# TOOLKIT_CON_ETIQ.net
KiCad netlist of a schematic drawn in EAGLE
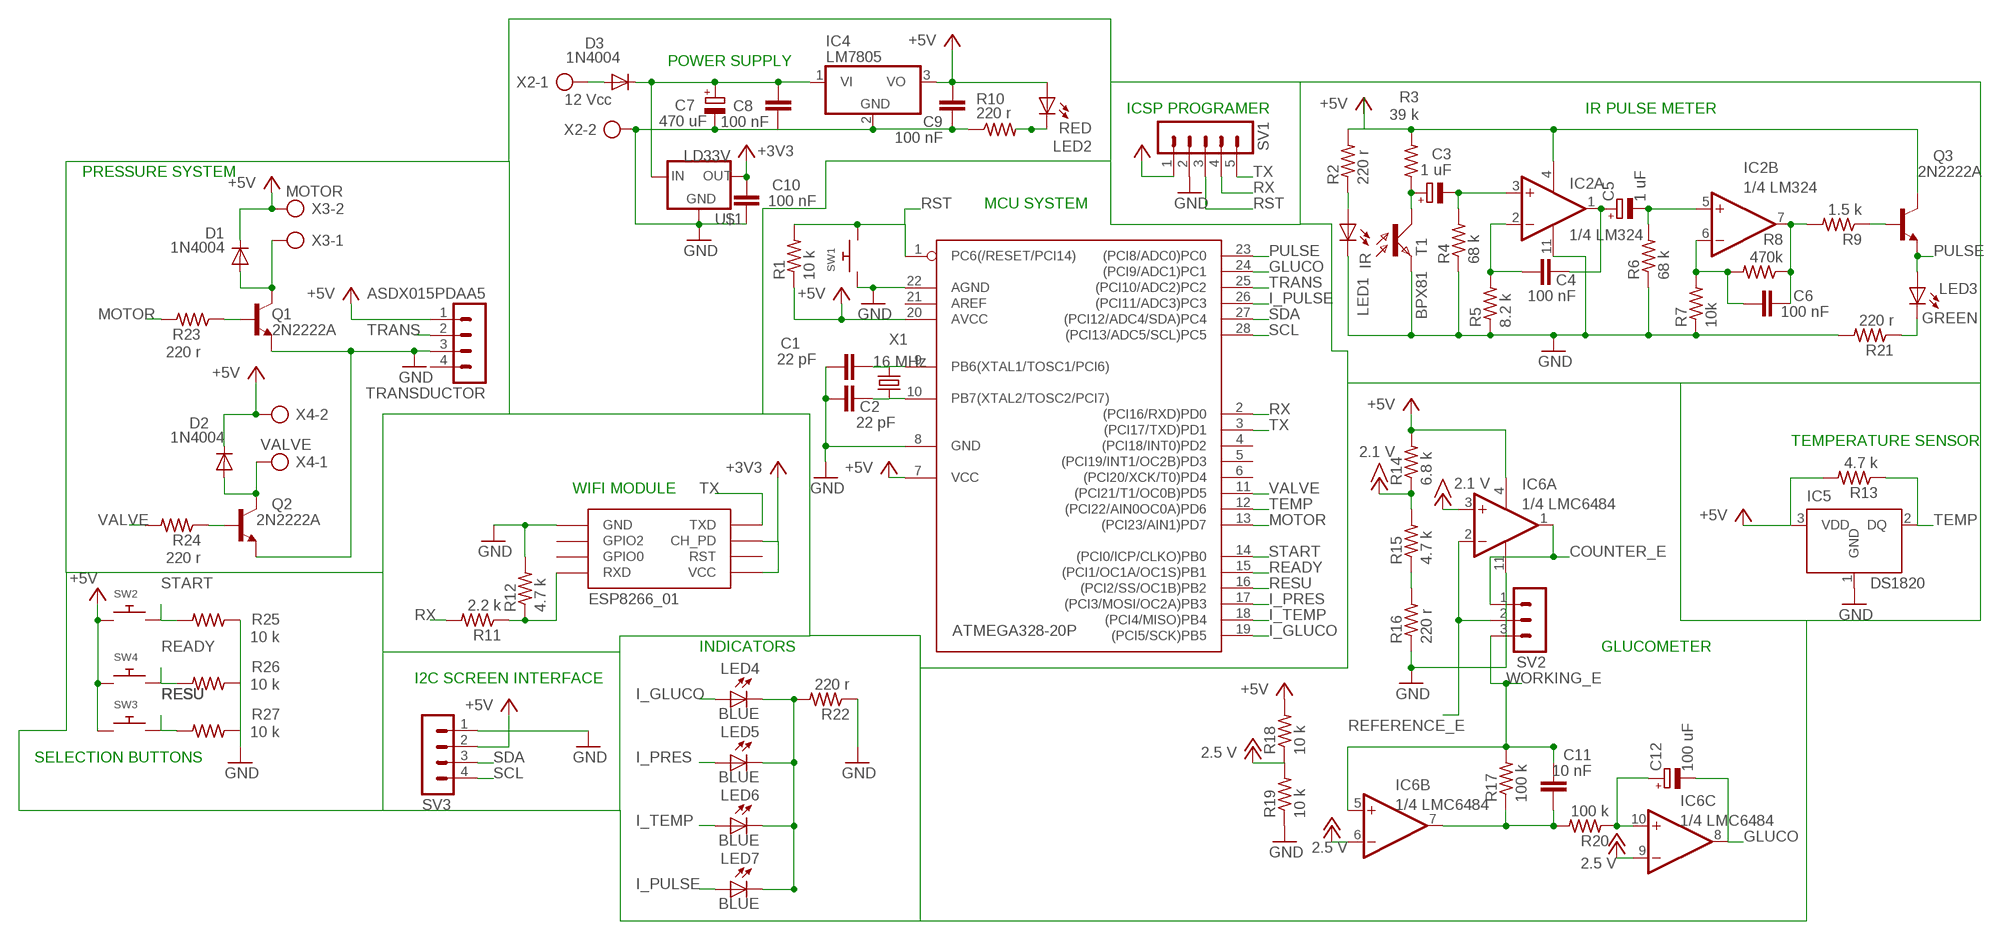
[diagram p0: schematic, sheet 1]

(export (version "E")
  (design (tool "Eeschema 10.0.6"))
  (components
    (comp (ref "C1")
      (value "22 pF")
      (footprint "eagle-import:C050-024X044")
      (libsource (lib "eagle-import") (part "C-EU050-024X044"))
    )
    (comp (ref "C2")
      (value "22 pF")
      (footprint "eagle-import:C050-024X044")
      (libsource (lib "eagle-import") (part "C-EU050-024X044"))
    )
    (comp (ref "C3")
      (value "1 uF")
      (footprint "eagle-import:E2,5-6E")
      (libsource (lib "eagle-import") (part "CPOL-EUE2,5-6E"))
    )
    (comp (ref "C4")
      (value "100 nF")
      (footprint "eagle-import:C050-025X075")
      (libsource (lib "eagle-import") (part "C-EU050-025X075"))
    )
    (comp (ref "C5")
      (value "1 uF")
      (footprint "eagle-import:E2,5-6E")
      (libsource (lib "eagle-import") (part "CPOL-EUE2,5-6E"))
    )
    (comp (ref "C6")
      (value "100 nF")
      (footprint "eagle-import:C050-025X075")
      (libsource (lib "eagle-import") (part "C-EU050-025X075"))
    )
    (comp (ref "C7")
      (value "470 uF")
      (footprint "eagle-import:E2,5-6E")
      (libsource (lib "eagle-import") (part "CPOL-EUE2,5-6E"))
    )
    (comp (ref "C8")
      (value "100 nF")
      (footprint "eagle-import:C050-025X075")
      (libsource (lib "eagle-import") (part "C-EU050-025X075"))
    )
    (comp (ref "C9")
      (value "100 nF")
      (footprint "eagle-import:C050-025X075")
      (libsource (lib "eagle-import") (part "C-EU050-025X075"))
    )
    (comp (ref "C10")
      (value "100 nF")
      (footprint "eagle-import:C050-025X075")
      (libsource (lib "eagle-import") (part "C-EU050-025X075"))
    )
    (comp (ref "C11")
      (value "10 nF")
      (footprint "eagle-import:C050-025X075")
      (libsource (lib "eagle-import") (part "C-EU050-025X075"))
    )
    (comp (ref "C12")
      (value "100 uF")
      (footprint "eagle-import:E2,5-6E")
      (libsource (lib "eagle-import") (part "CPOL-EUE2,5-6E"))
    )
    (comp (ref "D1")
      (value "1N4004")
      (footprint "eagle-import:DO41-10")
      (libsource (lib "eagle-import") (part "1N4004"))
    )
    (comp (ref "D2")
      (value "1N4004")
      (footprint "eagle-import:DO41-10")
      (libsource (lib "eagle-import") (part "1N4004"))
    )
    (comp (ref "D3")
      (value "1N4004")
      (footprint "eagle-import:DO41-10")
      (libsource (lib "eagle-import") (part "1N4004"))
    )
    (comp (ref "IC1")
      (value "ATMEGA328-20P")
      (footprint "eagle-import:DIL28-3")
      (libsource (lib "eagle-import") (part "ATMEGA328P-20"))
    )
    (comp (ref "IC2")
      (value "1/4 LM324")
      (footprint "eagle-import:DIL14")
      (libsource (lib "eagle-import") (part "LM324N"))
    )
    (comp (ref "IC4")
      (value "LM7805")
      (footprint "eagle-import:TO220V")
      (libsource (lib "eagle-import") (part "78TV05"))
    )
    (comp (ref "IC5")
      (value "DS1820")
      (footprint "eagle-import:TO-92")
      (libsource (lib "eagle-import") (part "DS1820"))
    )
    (comp (ref "IC6")
      (value "1/4 LMC6484")
      (footprint "eagle-import:DIL14")
      (libsource (lib "eagle-import") (part "LM2902N"))
    )
    (comp (ref "LED1")
      (value "IR")
      (footprint "eagle-import:LED3MM")
      (libsource (lib "eagle-import") (part "LED3MM"))
    )
    (comp (ref "LED2")
      (value "RED")
      (footprint "eagle-import:LED3MM")
      (libsource (lib "eagle-import") (part "LED3MM"))
    )
    (comp (ref "LED3")
      (value "GREEN")
      (footprint "eagle-import:LED3MM")
      (libsource (lib "eagle-import") (part "LED3MM"))
    )
    (comp (ref "LED4")
      (value "BLUE")
      (footprint "eagle-import:LED3MM")
      (libsource (lib "eagle-import") (part "LED3MM"))
    )
    (comp (ref "LED5")
      (value "BLUE")
      (footprint "eagle-import:LED3MM")
      (libsource (lib "eagle-import") (part "LED3MM"))
    )
    (comp (ref "LED6")
      (value "BLUE")
      (footprint "eagle-import:LED3MM")
      (libsource (lib "eagle-import") (part "LED3MM"))
    )
    (comp (ref "LED7")
      (value "BLUE")
      (footprint "eagle-import:LED3MM")
      (libsource (lib "eagle-import") (part "LED3MM"))
    )
    (comp (ref "Q1")
      (value "2N2222A")
      (footprint "eagle-import:TO92-EBC")
      (libsource (lib "eagle-import") (part "-NPN-TO92-EBC2N2222"))
    )
    (comp (ref "Q2")
      (value "2N2222A")
      (footprint "eagle-import:TO92-EBC")
      (libsource (lib "eagle-import") (part "-NPN-TO92-EBC2N2222"))
    )
    (comp (ref "Q3")
      (value "2N2222A")
      (footprint "eagle-import:TO92-EBC")
      (libsource (lib "eagle-import") (part "-NPN-TO92-EBC2N2222"))
    )
    (comp (ref "R1")
      (value "10 k")
      (footprint "eagle-import:0207_10")
      (libsource (lib "eagle-import") (part "R-US_0207/10"))
    )
    (comp (ref "R2")
      (value "220 r")
      (footprint "eagle-import:0207_10")
      (libsource (lib "eagle-import") (part "R-US_0207/10"))
    )
    (comp (ref "R3")
      (value "39 k")
      (footprint "eagle-import:0207_10")
      (libsource (lib "eagle-import") (part "R-US_0207/10"))
    )
    (comp (ref "R4")
      (value "68 k")
      (footprint "eagle-import:0207_10")
      (libsource (lib "eagle-import") (part "R-US_0207/10"))
    )
    (comp (ref "R5")
      (value "8.2 k")
      (footprint "eagle-import:0207_10")
      (libsource (lib "eagle-import") (part "R-US_0207/10"))
    )
    (comp (ref "R6")
      (value "68 k")
      (footprint "eagle-import:0207_10")
      (libsource (lib "eagle-import") (part "R-US_0207/10"))
    )
    (comp (ref "R7")
      (value "10k")
      (footprint "eagle-import:0207_10")
      (libsource (lib "eagle-import") (part "R-US_0207/10"))
    )
    (comp (ref "R8")
      (value "470k")
      (footprint "eagle-import:0207_10")
      (libsource (lib "eagle-import") (part "R-US_0207/10"))
    )
    (comp (ref "R9")
      (value "1.5 k")
      (footprint "eagle-import:0207_10")
      (libsource (lib "eagle-import") (part "R-US_0207/10"))
    )
    (comp (ref "R10")
      (value "220 r")
      (footprint "eagle-import:0207_10")
      (libsource (lib "eagle-import") (part "R-US_0207/10"))
    )
    (comp (ref "R11")
      (value "2.2 k")
      (footprint "eagle-import:0207_10")
      (libsource (lib "eagle-import") (part "R-US_0207/10"))
    )
    (comp (ref "R12")
      (value "4.7 k")
      (footprint "eagle-import:0207_10")
      (libsource (lib "eagle-import") (part "R-US_0207/10"))
    )
    (comp (ref "R13")
      (value "4.7 k")
      (footprint "eagle-import:0207_10")
      (libsource (lib "eagle-import") (part "R-US_0207/10"))
    )
    (comp (ref "R14")
      (value "6.8 k")
      (footprint "eagle-import:0207_10")
      (libsource (lib "eagle-import") (part "R-US_0207/10"))
    )
    (comp (ref "R15")
      (value "4.7 k")
      (footprint "eagle-import:0207_10")
      (libsource (lib "eagle-import") (part "R-US_0207/10"))
    )
    (comp (ref "R16")
      (value "220 r")
      (footprint "eagle-import:0207_10")
      (libsource (lib "eagle-import") (part "R-US_0207/10"))
    )
    (comp (ref "R17")
      (value "100 k")
      (footprint "eagle-import:0207_10")
      (libsource (lib "eagle-import") (part "R-US_0207/10"))
    )
    (comp (ref "R18")
      (value "10 k")
      (footprint "eagle-import:0207_10")
      (libsource (lib "eagle-import") (part "R-US_0207/10"))
    )
    (comp (ref "R19")
      (value "10 k")
      (footprint "eagle-import:0207_10")
      (libsource (lib "eagle-import") (part "R-US_0207/10"))
    )
    (comp (ref "R20")
      (value "100 k")
      (footprint "eagle-import:0207_10")
      (libsource (lib "eagle-import") (part "R-US_0207/10"))
    )
    (comp (ref "R21")
      (value "220 r")
      (footprint "eagle-import:0207_10")
      (libsource (lib "eagle-import") (part "R-US_0207/10"))
    )
    (comp (ref "R22")
      (value "220 r")
      (footprint "eagle-import:0207_10")
      (libsource (lib "eagle-import") (part "R-US_0207/10"))
    )
    (comp (ref "R23")
      (value "220 r")
      (footprint "eagle-import:0207_10")
      (libsource (lib "eagle-import") (part "R-US_0207/10"))
    )
    (comp (ref "R24")
      (value "220 r")
      (footprint "eagle-import:0207_10")
      (libsource (lib "eagle-import") (part "R-US_0207/10"))
    )
    (comp (ref "R25")
      (value "10 k")
      (footprint "eagle-import:0207_10")
      (libsource (lib "eagle-import") (part "R-US_0207/10"))
    )
    (comp (ref "R26")
      (value "10 k")
      (footprint "eagle-import:0207_10")
      (libsource (lib "eagle-import") (part "R-US_0207/10"))
    )
    (comp (ref "R27")
      (value "10 k")
      (footprint "eagle-import:0207_10")
      (libsource (lib "eagle-import") (part "R-US_0207/10"))
    )
    (comp (ref "SV1")
      (value "MA05-1")
      (footprint "eagle-import:MA05-1")
      (libsource (lib "eagle-import") (part "MA05-1"))
    )
    (comp (ref "SV2")
      (value "MA03-1")
      (footprint "eagle-import:MA03-1")
      (libsource (lib "eagle-import") (part "MA03-1"))
    )
    (comp (ref "SV3")
      (value "MA04-1")
      (footprint "eagle-import:MA04-1")
      (libsource (lib "eagle-import") (part "MA04-1"))
    )
    (comp (ref "SW1")
      (value "SWITCH_PUSHBUTTONEVQ-PE")
      (footprint "eagle-import:TACT_PANA-EVQ")
      (libsource (lib "eagle-import") (part "SWITCH_PUSHBUTTONEVQ-PE"))
    )
    (comp (ref "SW2")
      (value "SWITCH_PUSHBUTTONEVQ-PE")
      (footprint "eagle-import:TACT_PANA-EVQ")
      (libsource (lib "eagle-import") (part "SWITCH_PUSHBUTTONEVQ-PE"))
    )
    (comp (ref "SW3")
      (value "SWITCH_PUSHBUTTONEVQ-PE")
      (footprint "eagle-import:TACT_PANA-EVQ")
      (libsource (lib "eagle-import") (part "SWITCH_PUSHBUTTONEVQ-PE"))
    )
    (comp (ref "SW4")
      (value "SWITCH_PUSHBUTTONEVQ-PE")
      (footprint "eagle-import:TACT_PANA-EVQ")
      (libsource (lib "eagle-import") (part "SWITCH_PUSHBUTTONEVQ-PE"))
    )
    (comp (ref "T1")
      (value "BPX81")
      (footprint "eagle-import:BPX81")
      (libsource (lib "eagle-import") (part "BPX81"))
    )
    (comp (ref "TRANSDUCTOR")
      (value "ASDX015PDAA5")
      (footprint "eagle-import:MA04-1")
      (libsource (lib "eagle-import") (part "MA04-1"))
    )
    (comp (ref "U$1")
      (value "LD33V")
      (footprint "eagle-import:LD1117V33")
      (libsource (lib "eagle-import") (part "LD1117V33"))
    )
    (comp (ref "U$2")
      (value "ESP8266_01")
      (footprint "eagle-import:ESP01")
      (libsource (lib "eagle-import") (part "ESP01"))
    )
    (comp (ref "X1")
      (value "16 MHz")
      (footprint "eagle-import:HC18U-V")
      (libsource (lib "eagle-import") (part "CRYSTALHC18U-V"))
    )
    (comp (ref "X2")
      (value "12 Vcc")
      (footprint "eagle-import:AK500_2")
      (libsource (lib "eagle-import") (part "AK500/2"))
    )
    (comp (ref "X3")
      (value "MOTOR")
      (footprint "eagle-import:AK500_2")
      (libsource (lib "eagle-import") (part "AK500/2"))
    )
    (comp (ref "X4")
      (value "VALVE")
      (footprint "eagle-import:AK500_2")
      (libsource (lib "eagle-import") (part "AK500/2"))
    )
  )
  (nets
    (net (code "1") (name "+3V3") (class "Default")
      (node (ref "C10") (pin "2") (pinfunction "2_2") (pintype "passive"))
      (node (ref "U$1") (pin "OUT") (pinfunction "OUT_OUT") (pintype "output"))
      (node (ref "U$2") (pin "CH_PD") (pinfunction "CH_PD_CH_PD") (pintype "bidirectional"))
      (node (ref "U$2") (pin "VCC") (pinfunction "VCC_VCC") (pintype "bidirectional"))
    )
    (net (code "2") (name "+5V") (class "Default")
      (node (ref "C9") (pin "2") (pinfunction "2_2") (pintype "passive"))
      (node (ref "D1") (pin "C") (pinfunction "C_C") (pintype "passive"))
      (node (ref "D2") (pin "C") (pinfunction "C_C") (pintype "passive"))
      (node (ref "IC1") (pin "20") (pinfunction "AVCC_20") (pintype "bidirectional"))
      (node (ref "IC1") (pin "7") (pinfunction "VCC_7") (pintype "bidirectional"))
      (node (ref "IC2") (pin "4") (pinfunction "V+_4") (pintype "power_in"))
      (node (ref "IC4") (pin "3") (pinfunction "VO_3") (pintype "passive"))
      (node (ref "IC5") (pin "3") (pinfunction "VDD_3") (pintype "input"))
      (node (ref "IC6") (pin "4") (pinfunction "V+_4") (pintype "power_in"))
      (node (ref "LED2") (pin "A") (pinfunction "A_A") (pintype "passive"))
      (node (ref "Q3") (pin "C") (pinfunction "C_C") (pintype "passive"))
      (node (ref "R1") (pin "1") (pinfunction "1_1") (pintype "passive"))
      (node (ref "R13") (pin "2") (pinfunction "2_2") (pintype "passive"))
      (node (ref "R14") (pin "2") (pinfunction "2_2") (pintype "passive"))
      (node (ref "R18") (pin "2") (pinfunction "2_2") (pintype "passive"))
      (node (ref "R2") (pin "2") (pinfunction "2_2") (pintype "passive"))
      (node (ref "R3") (pin "2") (pinfunction "2_2") (pintype "passive"))
      (node (ref "SV1") (pin "1") (pinfunction "1_1") (pintype "passive"))
      (node (ref "SV3") (pin "2") (pinfunction "2_2") (pintype "passive"))
      (node (ref "SW2") (pin "P$1") (pinfunction "P$1_P$1") (pintype "passive"))
      (node (ref "SW3") (pin "P$1") (pinfunction "P$1_P$1") (pintype "passive"))
      (node (ref "SW4") (pin "P$1") (pinfunction "P$1_P$1") (pintype "passive"))
      (node (ref "TRANSDUCTOR") (pin "1") (pinfunction "1_1") (pintype "passive"))
      (node (ref "X3") (pin "2") (pinfunction "KL_2") (pintype "passive"))
      (node (ref "X4") (pin "2") (pinfunction "KL_2") (pintype "passive"))
    )
    (net (code "3") (name "/COUNTER_E") (class "Default")
      (node (ref "IC6") (pin "1") (pinfunction "OUT_1") (pintype "output"))
      (node (ref "SV2") (pin "1") (pinfunction "1_1") (pintype "passive"))
    )
    (net (code "4") (name "/GLUCO") (class "Default")
      (node (ref "C12") (pin "-") (pinfunction "-_-") (pintype "passive"))
      (node (ref "IC1") (pin "24") (pinfunction "(PCI9/ADC1)PC1_24") (pintype "bidirectional"))
      (node (ref "IC6") (pin "8") (pinfunction "OUT_8") (pintype "output"))
    )
    (net (code "5") (name "/I_GLUCO") (class "Default")
      (node (ref "IC1") (pin "19") (pinfunction "(PCI5/SCK)PB5_19") (pintype "bidirectional"))
      (node (ref "LED4") (pin "A") (pinfunction "A_A") (pintype "passive"))
    )
    (net (code "6") (name "/I_PRES") (class "Default")
      (node (ref "IC1") (pin "17") (pinfunction "(PCI3/MOSI/OC2A)PB3_17") (pintype "bidirectional"))
      (node (ref "LED5") (pin "A") (pinfunction "A_A") (pintype "passive"))
    )
    (net (code "7") (name "/I_PULSE") (class "Default")
      (node (ref "IC1") (pin "26") (pinfunction "(PCI11/ADC3)PC3_26") (pintype "bidirectional"))
      (node (ref "LED7") (pin "A") (pinfunction "A_A") (pintype "passive"))
    )
    (net (code "8") (name "/I_TEMP") (class "Default")
      (node (ref "IC1") (pin "18") (pinfunction "(PCI4/MISO)PB4_18") (pintype "bidirectional"))
      (node (ref "LED6") (pin "A") (pinfunction "A_A") (pintype "passive"))
    )
    (net (code "9") (name "/MOTOR") (class "Default")
      (node (ref "IC1") (pin "13") (pinfunction "(PCI23/AIN1)PD7_13") (pintype "bidirectional"))
      (node (ref "R23") (pin "2") (pinfunction "2_2") (pintype "passive"))
    )
    (net (code "10") (name "/PULSE") (class "Default")
      (node (ref "IC1") (pin "23") (pinfunction "(PCI8/ADC0)PC0_23") (pintype "bidirectional"))
      (node (ref "LED3") (pin "A") (pinfunction "A_A") (pintype "passive"))
      (node (ref "Q3") (pin "E") (pinfunction "E_E") (pintype "passive"))
    )
    (net (code "11") (name "/READY") (class "Default")
      (node (ref "IC1") (pin "15") (pinfunction "(PCI1/OC1A/OC1S)PB1_15") (pintype "bidirectional"))
      (node (ref "R26") (pin "2") (pinfunction "2_2") (pintype "passive"))
      (node (ref "SW4") (pin "P$2") (pinfunction "P$2_P$2") (pintype "passive"))
    )
    (net (code "12") (name "/REFERENCE_E") (class "Default")
      (node (ref "IC6") (pin "2") (pinfunction "-IN_2") (pintype "input"))
      (node (ref "SV2") (pin "2") (pinfunction "2_2") (pintype "passive"))
    )
    (net (code "13") (name "/RESU") (class "Default")
      (node (ref "IC1") (pin "16") (pinfunction "(PCI2/SS/OC1B)PB2_16") (pintype "bidirectional"))
      (node (ref "R27") (pin "2") (pinfunction "2_2") (pintype "passive"))
      (node (ref "SW3") (pin "P$2") (pinfunction "P$2_P$2") (pintype "passive"))
    )
    (net (code "14") (name "/RST") (class "Default")
      (node (ref "IC1") (pin "1") (pinfunction "PC6(/RESET/PCI14)_1") (pintype "bidirectional"))
      (node (ref "R1") (pin "2") (pinfunction "2_2") (pintype "passive"))
      (node (ref "SV1") (pin "3") (pinfunction "3_3") (pintype "passive"))
      (node (ref "SW1") (pin "P$2") (pinfunction "P$2_P$2") (pintype "passive"))
    )
    (net (code "15") (name "/RX") (class "Default")
      (node (ref "IC1") (pin "2") (pinfunction "(PCI16/RXD)PD0_2") (pintype "bidirectional"))
      (node (ref "R11") (pin "2") (pinfunction "2_2") (pintype "passive"))
      (node (ref "SV1") (pin "4") (pinfunction "4_4") (pintype "passive"))
    )
    (net (code "16") (name "/SCL") (class "Default")
      (node (ref "IC1") (pin "28") (pinfunction "(PCI13/ADC5/SCL)PC5_28") (pintype "bidirectional"))
      (node (ref "SV3") (pin "4") (pinfunction "4_4") (pintype "passive"))
    )
    (net (code "17") (name "/SDA") (class "Default")
      (node (ref "IC1") (pin "27") (pinfunction "(PCI12/ADC4/SDA)PC4_27") (pintype "bidirectional"))
      (node (ref "SV3") (pin "3") (pinfunction "3_3") (pintype "passive"))
    )
    (net (code "18") (name "/START") (class "Default")
      (node (ref "IC1") (pin "14") (pinfunction "(PCI0/ICP/CLKO)PB0_14") (pintype "bidirectional"))
      (node (ref "R25") (pin "2") (pinfunction "2_2") (pintype "passive"))
      (node (ref "SW2") (pin "P$2") (pinfunction "P$2_P$2") (pintype "passive"))
    )
    (net (code "19") (name "/TEMP") (class "Default")
      (node (ref "IC1") (pin "12") (pinfunction "(PCI22/AIN0OC0A)PD6_12") (pintype "bidirectional"))
      (node (ref "IC5") (pin "2") (pinfunction "DQ_2") (pintype "output"))
      (node (ref "R13") (pin "1") (pinfunction "1_1") (pintype "passive"))
    )
    (net (code "20") (name "/TRANS") (class "Default")
      (node (ref "IC1") (pin "25") (pinfunction "(PCI10/ADC2)PC2_25") (pintype "bidirectional"))
      (node (ref "TRANSDUCTOR") (pin "2") (pinfunction "2_2") (pintype "passive"))
    )
    (net (code "21") (name "/TX") (class "Default")
      (node (ref "IC1") (pin "3") (pinfunction "(PCI17/TXD)PD1_3") (pintype "bidirectional"))
      (node (ref "SV1") (pin "5") (pinfunction "5_5") (pintype "passive"))
      (node (ref "U$2") (pin "TX") (pinfunction "TXD_TX") (pintype "bidirectional"))
    )
    (net (code "22") (name "/VALVE") (class "Default")
      (node (ref "IC1") (pin "11") (pinfunction "(PCI21/T1/OC0B)PD5_11") (pintype "bidirectional"))
      (node (ref "R24") (pin "2") (pinfunction "2_2") (pintype "passive"))
    )
    (net (code "23") (name "/WORKING_E") (class "Default")
      (node (ref "C11") (pin "2") (pinfunction "2_2") (pintype "passive"))
      (node (ref "IC6") (pin "5") (pinfunction "+IN_5") (pintype "input"))
      (node (ref "R17") (pin "2") (pinfunction "2_2") (pintype "passive"))
      (node (ref "SV2") (pin "3") (pinfunction "3_3") (pintype "passive"))
    )
    (net (code "24") (name "2.1 V") (class "Default")
      (node (ref "IC6") (pin "3") (pinfunction "+IN_3") (pintype "input"))
      (node (ref "R14") (pin "1") (pinfunction "1_1") (pintype "passive"))
      (node (ref "R15") (pin "2") (pinfunction "2_2") (pintype "passive"))
    )
    (net (code "25") (name "2.5 V") (class "Default")
      (node (ref "IC6") (pin "6") (pinfunction "-IN_6") (pintype "input"))
      (node (ref "IC6") (pin "9") (pinfunction "-IN_9") (pintype "input"))
      (node (ref "R18") (pin "1") (pinfunction "1_1") (pintype "passive"))
      (node (ref "R19") (pin "2") (pinfunction "2_2") (pintype "passive"))
    )
    (net (code "26") (name "GND") (class "Default")
      (node (ref "C1") (pin "1") (pinfunction "1_1") (pintype "passive"))
      (node (ref "C10") (pin "1") (pinfunction "1_1") (pintype "passive"))
      (node (ref "C2") (pin "1") (pinfunction "1_1") (pintype "passive"))
      (node (ref "C7") (pin "-") (pinfunction "-_-") (pintype "passive"))
      (node (ref "C8") (pin "1") (pinfunction "1_1") (pintype "passive"))
      (node (ref "C9") (pin "1") (pinfunction "1_1") (pintype "passive"))
      (node (ref "IC1") (pin "22") (pinfunction "AGND_22") (pintype "bidirectional"))
      (node (ref "IC1") (pin "8") (pinfunction "GND_8") (pintype "bidirectional"))
      (node (ref "IC2") (pin "11") (pinfunction "V-_11") (pintype "power_in"))
      (node (ref "IC4") (pin "2") (pinfunction "GND_2") (pintype "passive"))
      (node (ref "IC5") (pin "1") (pinfunction "GND_1") (pintype "power_in"))
      (node (ref "IC6") (pin "11") (pinfunction "V-_11") (pintype "power_in"))
      (node (ref "LED1") (pin "K") (pinfunction "C_K") (pintype "passive"))
      (node (ref "Q1") (pin "E") (pinfunction "E_E") (pintype "passive"))
      (node (ref "Q2") (pin "E") (pinfunction "E_E") (pintype "passive"))
      (node (ref "R10") (pin "1") (pinfunction "1_1") (pintype "passive"))
      (node (ref "R12") (pin "2") (pinfunction "2_2") (pintype "passive"))
      (node (ref "R16") (pin "1") (pinfunction "1_1") (pintype "passive"))
      (node (ref "R19") (pin "1") (pinfunction "1_1") (pintype "passive"))
      (node (ref "R21") (pin "2") (pinfunction "2_2") (pintype "passive"))
      (node (ref "R22") (pin "1") (pinfunction "1_1") (pintype "passive"))
      (node (ref "R25") (pin "1") (pinfunction "1_1") (pintype "passive"))
      (node (ref "R26") (pin "1") (pinfunction "1_1") (pintype "passive"))
      (node (ref "R27") (pin "1") (pinfunction "1_1") (pintype "passive"))
      (node (ref "R4") (pin "1") (pinfunction "1_1") (pintype "passive"))
      (node (ref "R5") (pin "1") (pinfunction "1_1") (pintype "passive"))
      (node (ref "R6") (pin "1") (pinfunction "1_1") (pintype "passive"))
      (node (ref "R7") (pin "1") (pinfunction "1_1") (pintype "passive"))
      (node (ref "SV1") (pin "2") (pinfunction "2_2") (pintype "passive"))
      (node (ref "SV3") (pin "1") (pinfunction "1_1") (pintype "passive"))
      (node (ref "SW1") (pin "P$1") (pinfunction "P$1_P$1") (pintype "passive"))
      (node (ref "T1") (pin "E") (pinfunction "E_E") (pintype "passive"))
      (node (ref "TRANSDUCTOR") (pin "3") (pinfunction "3_3") (pintype "passive"))
      (node (ref "U$1") (pin "GND") (pinfunction "GND_GND") (pintype "input"))
      (node (ref "U$2") (pin "GND") (pinfunction "GND_GND") (pintype "bidirectional"))
      (node (ref "X2") (pin "2") (pinfunction "KL_2") (pintype "passive"))
    )
    (net (code "27") (name "Net-(C3-Pad+)") (class "Default")
      (node (ref "C3") (pin "+") (pinfunction "+_+") (pintype "passive"))
      (node (ref "R3") (pin "1") (pinfunction "1_1") (pintype "passive"))
      (node (ref "T1") (pin "C") (pinfunction "C_C") (pintype "passive"))
    )
    (net (code "28") (name "Net-(IC1-PB6(XTAL1{slash}TOSC1{slash}PCI6))") (class "Default")
      (node (ref "C1") (pin "2") (pinfunction "2_2") (pintype "passive"))
      (node (ref "IC1") (pin "9") (pinfunction "PB6(XTAL1/TOSC1/PCI6)_9") (pintype "bidirectional"))
      (node (ref "X1") (pin "1") (pinfunction "1_1") (pintype "passive"))
    )
    (net (code "29") (name "Net-(IC1-PB7(XTAL2{slash}TOSC2{slash}PCI7))") (class "Default")
      (node (ref "C2") (pin "2") (pinfunction "2_2") (pintype "passive"))
      (node (ref "IC1") (pin "10") (pinfunction "PB7(XTAL2/TOSC2/PCI7)_10") (pintype "bidirectional"))
      (node (ref "X1") (pin "2") (pinfunction "2_2") (pintype "passive"))
    )
    (net (code "30") (name "Net-(IC2A-+IN)") (class "Default")
      (node (ref "C3") (pin "-") (pinfunction "-_-") (pintype "passive"))
      (node (ref "IC2") (pin "3") (pinfunction "+IN_3") (pintype "input"))
      (node (ref "R4") (pin "2") (pinfunction "2_2") (pintype "passive"))
    )
    (net (code "31") (name "Net-(IC2A--IN)") (class "Default")
      (node (ref "C4") (pin "1") (pinfunction "1_1") (pintype "passive"))
      (node (ref "IC2") (pin "2") (pinfunction "-IN_2") (pintype "input"))
      (node (ref "R5") (pin "2") (pinfunction "2_2") (pintype "passive"))
    )
    (net (code "32") (name "Net-(IC2A-OUT)") (class "Default")
      (node (ref "C4") (pin "2") (pinfunction "2_2") (pintype "passive"))
      (node (ref "C5") (pin "+") (pinfunction "+_+") (pintype "passive"))
      (node (ref "IC2") (pin "1") (pinfunction "OUT_1") (pintype "output"))
    )
    (net (code "33") (name "Net-(IC2B-+IN)") (class "Default")
      (node (ref "C5") (pin "-") (pinfunction "-_-") (pintype "passive"))
      (node (ref "IC2") (pin "5") (pinfunction "+IN_5") (pintype "input"))
      (node (ref "R6") (pin "2") (pinfunction "2_2") (pintype "passive"))
    )
    (net (code "34") (name "Net-(IC2B--IN)") (class "Default")
      (node (ref "C6") (pin "1") (pinfunction "1_1") (pintype "passive"))
      (node (ref "IC2") (pin "6") (pinfunction "-IN_6") (pintype "input"))
      (node (ref "R7") (pin "2") (pinfunction "2_2") (pintype "passive"))
      (node (ref "R8") (pin "2") (pinfunction "2_2") (pintype "passive"))
    )
    (net (code "35") (name "Net-(IC2B-OUT)") (class "Default")
      (node (ref "C6") (pin "2") (pinfunction "2_2") (pintype "passive"))
      (node (ref "IC2") (pin "7") (pinfunction "OUT_7") (pintype "output"))
      (node (ref "R8") (pin "1") (pinfunction "1_1") (pintype "passive"))
      (node (ref "R9") (pin "2") (pinfunction "2_2") (pintype "passive"))
    )
    (net (code "36") (name "Net-(IC4-VI)") (class "Default")
      (node (ref "C7") (pin "+") (pinfunction "+_+") (pintype "passive"))
      (node (ref "C8") (pin "2") (pinfunction "2_2") (pintype "passive"))
      (node (ref "D3") (pin "C") (pinfunction "C_C") (pintype "passive"))
      (node (ref "IC4") (pin "1") (pinfunction "VI_1") (pintype "input"))
      (node (ref "U$1") (pin "IN") (pinfunction "IN_IN") (pintype "input"))
    )
    (net (code "37") (name "Net-(IC6B-OUT)") (class "Default")
      (node (ref "C11") (pin "1") (pinfunction "1_1") (pintype "passive"))
      (node (ref "IC6") (pin "7") (pinfunction "OUT_7") (pintype "output"))
      (node (ref "R17") (pin "1") (pinfunction "1_1") (pintype "passive"))
      (node (ref "R20") (pin "2") (pinfunction "2_2") (pintype "passive"))
    )
    (net (code "38") (name "Net-(IC6C-+IN)") (class "Default")
      (node (ref "C12") (pin "+") (pinfunction "+_+") (pintype "passive"))
      (node (ref "IC6") (pin "10") (pinfunction "+IN_10") (pintype "input"))
      (node (ref "R20") (pin "1") (pinfunction "1_1") (pintype "passive"))
    )
    (net (code "39") (name "Net-(LED1-PadA)") (class "Default")
      (node (ref "LED1") (pin "A") (pinfunction "A_A") (pintype "passive"))
      (node (ref "R2") (pin "1") (pinfunction "1_1") (pintype "passive"))
    )
    (net (code "40") (name "Net-(LED2-C)") (class "Default")
      (node (ref "LED2") (pin "K") (pinfunction "C_K") (pintype "passive"))
      (node (ref "R10") (pin "2") (pinfunction "2_2") (pintype "passive"))
    )
    (net (code "41") (name "Net-(LED3-C)") (class "Default")
      (node (ref "LED3") (pin "K") (pinfunction "C_K") (pintype "passive"))
      (node (ref "R21") (pin "1") (pinfunction "1_1") (pintype "passive"))
    )
    (net (code "42") (name "Net-(LED4-C)") (class "Default")
      (node (ref "LED4") (pin "K") (pinfunction "C_K") (pintype "passive"))
      (node (ref "LED5") (pin "K") (pinfunction "C_K") (pintype "passive"))
      (node (ref "LED6") (pin "K") (pinfunction "C_K") (pintype "passive"))
      (node (ref "LED7") (pin "K") (pinfunction "C_K") (pintype "passive"))
      (node (ref "R22") (pin "2") (pinfunction "2_2") (pintype "passive"))
    )
    (net (code "43") (name "Net-(Q1-PadB)") (class "Default")
      (node (ref "Q1") (pin "B") (pinfunction "B_B") (pintype "passive"))
      (node (ref "R23") (pin "1") (pinfunction "1_1") (pintype "passive"))
    )
    (net (code "44") (name "Net-(Q2-PadB)") (class "Default")
      (node (ref "Q2") (pin "B") (pinfunction "B_B") (pintype "passive"))
      (node (ref "R24") (pin "1") (pinfunction "1_1") (pintype "passive"))
    )
    (net (code "45") (name "Net-(Q3-PadB)") (class "Default")
      (node (ref "Q3") (pin "B") (pinfunction "B_B") (pintype "passive"))
      (node (ref "R9") (pin "1") (pinfunction "1_1") (pintype "passive"))
    )
    (net (code "46") (name "Net-(R15-Pad1)") (class "Default")
      (node (ref "R15") (pin "1") (pinfunction "1_1") (pintype "passive"))
      (node (ref "R16") (pin "2") (pinfunction "2_2") (pintype "passive"))
    )
    (net (code "47") (name "Net-(U$2-RXD)") (class "Default")
      (node (ref "R11") (pin "1") (pinfunction "1_1") (pintype "passive"))
      (node (ref "R12") (pin "1") (pinfunction "1_1") (pintype "passive"))
      (node (ref "U$2") (pin "RX") (pinfunction "RXD_RX") (pintype "bidirectional"))
    )
    (net (code "48") (name "Net-(X2A-KL)") (class "Default")
      (node (ref "D3") (pin "A") (pinfunction "A_A") (pintype "passive"))
      (node (ref "X2") (pin "1") (pinfunction "KL_1") (pintype "passive"))
    )
    (net (code "49") (name "Net-(X3A-KL)") (class "Default")
      (node (ref "D1") (pin "A") (pinfunction "A_A") (pintype "passive"))
      (node (ref "Q1") (pin "C") (pinfunction "C_C") (pintype "passive"))
      (node (ref "X3") (pin "1") (pinfunction "KL_1") (pintype "passive"))
    )
    (net (code "50") (name "Net-(X4A-KL)") (class "Default")
      (node (ref "D2") (pin "A") (pinfunction "A_A") (pintype "passive"))
      (node (ref "Q2") (pin "C") (pinfunction "C_C") (pintype "passive"))
      (node (ref "X4") (pin "1") (pinfunction "KL_1") (pintype "passive"))
    )
    (net (code "51") (name "unconnected-(IC1-(PCI18{slash}INT0)PD2-Pad4)") (class "Default")
      (node (ref "IC1") (pin "4") (pinfunction "(PCI18/INT0)PD2_4") (pintype "bidirectional"))
    )
    (net (code "52") (name "unconnected-(IC1-(PCI19{slash}INT1{slash}OC2B)PD3-Pad5)") (class "Default")
      (node (ref "IC1") (pin "5") (pinfunction "(PCI19/INT1/OC2B)PD3_5") (pintype "bidirectional"))
    )
    (net (code "53") (name "unconnected-(IC1-(PCI20{slash}XCK{slash}T0)PD4-Pad6)") (class "Default")
      (node (ref "IC1") (pin "6") (pinfunction "(PCI20/XCK/T0)PD4_6") (pintype "bidirectional"))
    )
    (net (code "54") (name "unconnected-(IC1-AREF-Pad21)") (class "Default")
      (node (ref "IC1") (pin "21") (pinfunction "AREF_21") (pintype "bidirectional"))
    )
    (net (code "55") (name "unconnected-(TRANSDUCTOR-Pad4)") (class "Default")
      (node (ref "TRANSDUCTOR") (pin "4") (pinfunction "4_4") (pintype "passive"))
    )
    (net (code "56") (name "unconnected-(U$2-PadGPIO0)") (class "Default")
      (node (ref "U$2") (pin "GPIO0") (pinfunction "GPIO0_GPIO0") (pintype "bidirectional"))
    )
    (net (code "57") (name "unconnected-(U$2-PadGPIO2)") (class "Default")
      (node (ref "U$2") (pin "GPIO2") (pinfunction "GPIO2_GPIO2") (pintype "bidirectional"))
    )
    (net (code "58") (name "unconnected-(U$2-PadRST)") (class "Default")
      (node (ref "U$2") (pin "RST") (pinfunction "RST_RST") (pintype "bidirectional"))
    )
  )
)
